# attiny85-ws2812b-v1.net
KiCad netlist of a schematic drawn in EAGLE
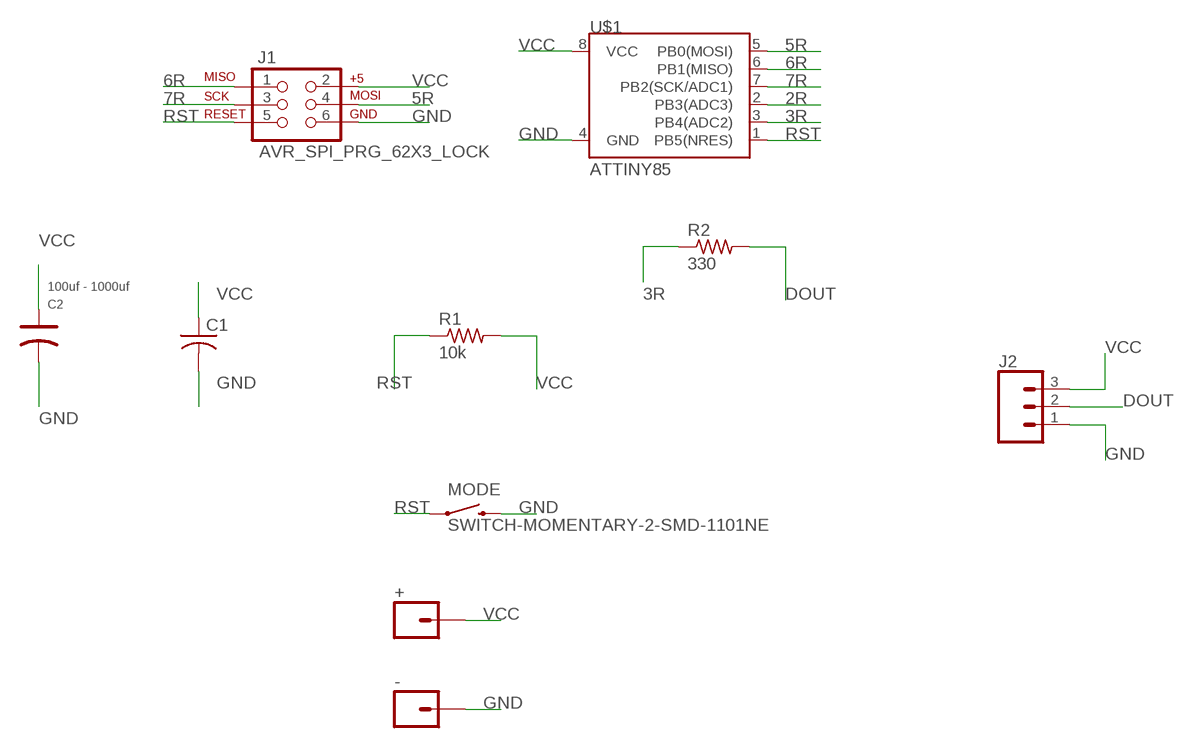
[diagram p0: schematic, sheet 1]

(export (version "E")
  (design (tool "Eeschema 10.0.6"))
  (components
    (comp (ref "+")
      (value "CONN_01PTH_LONGPAD")
      (footprint "eagle-import:1X01_LONGPAD")
      (libsource (lib "eagle-import") (part "CONN_01PTH_LONGPAD"))
    )
    (comp (ref "-")
      (value "CONN_01PTH_LONGPAD")
      (footprint "eagle-import:1X01_LONGPAD")
      (libsource (lib "eagle-import") (part "CONN_01PTH_LONGPAD"))
    )
    (comp (ref "C1")
      (value "C-USC0805K")
      (footprint "eagle-import:C0805K")
      (libsource (lib "eagle-import") (part "C-USC0805K"))
    )
    (comp (ref "C2")
      (value "100uf - 1000uf")
      (footprint "eagle-import:PC-D5.3MM")
      (fields (field (name "MPN") "KS 100uF/16V"))
      (libsource (lib "eagle-import") (part "DIP-ALUMINUM-100UF-16V(D5-H7MM)"))
    )
    (comp (ref "J1")
      (value "AVR_SPI_PRG_62X3_LOCK")
      (footprint "eagle-import:2X3_LOCK")
      (libsource (lib "eagle-import") (part "AVR_SPI_PRG_62X3_LOCK"))
    )
    (comp (ref "J2")
      (value "CONN_03LOCK_LONGPADS")
      (footprint "eagle-import:1X03_LOCK_LONGPADS")
      (libsource (lib "eagle-import") (part "CONN_03LOCK_LONGPADS"))
    )
    (comp (ref "MODE")
      (value "SWITCH-MOMENTARY-2-SMD-1101NE")
      (footprint "eagle-import:TACTILE-SWITCH-1101NE")
      (libsource (lib "eagle-import") (part "SWITCH-MOMENTARY-2-SMD-1101NE"))
    )
    (comp (ref "R1")
      (value "10k")
      (footprint "eagle-import:M0805")
      (libsource (lib "eagle-import") (part "R-US_M0805"))
    )
    (comp (ref "R2")
      (value "330")
      (footprint "eagle-import:M0805")
      (libsource (lib "eagle-import") (part "R-US_M0805"))
    )
    (comp (ref "U$1")
      (value "ATTINY85")
      (footprint "eagle-import:SO08-EIAJ")
      (libsource (lib "eagle-import") (part "ATTINY45"))
    )
  )
  (nets
    (net (code "1") (name "/2R") (class "Default")
      (node (ref "U$1") (pin "2") (pinfunction "PB3(ADC3)_2") (pintype "bidirectional"))
    )
    (net (code "2") (name "/3R") (class "Default")
      (node (ref "R2") (pin "1") (pinfunction "1_1") (pintype "passive"))
      (node (ref "U$1") (pin "3") (pinfunction "PB4(ADC2)_3") (pintype "bidirectional"))
    )
    (net (code "3") (name "/5R") (class "Default")
      (node (ref "J1") (pin "4") (pinfunction "4_4") (pintype "passive"))
      (node (ref "U$1") (pin "5") (pinfunction "PB0(MOSI)_5") (pintype "bidirectional"))
    )
    (net (code "4") (name "/6R") (class "Default")
      (node (ref "J1") (pin "1") (pinfunction "1_1") (pintype "passive"))
      (node (ref "U$1") (pin "6") (pinfunction "PB1(MISO)_6") (pintype "bidirectional"))
    )
    (net (code "5") (name "/7R") (class "Default")
      (node (ref "J1") (pin "3") (pinfunction "3_3") (pintype "passive"))
      (node (ref "U$1") (pin "7") (pinfunction "PB2(SCK/ADC1)_7") (pintype "bidirectional"))
    )
    (net (code "6") (name "/DOUT") (class "Default")
      (node (ref "J2") (pin "2") (pinfunction "2_2") (pintype "passive"))
      (node (ref "R2") (pin "2") (pinfunction "2_2") (pintype "passive"))
    )
    (net (code "7") (name "/GND") (class "Default")
      (node (ref "-") (pin "1") (pinfunction "1_1") (pintype "passive"))
      (node (ref "C1") (pin "2") (pinfunction "2_2") (pintype "passive"))
      (node (ref "C2") (pin "-") (pinfunction "-_-") (pintype "passive"))
      (node (ref "J1") (pin "6") (pinfunction "6_6") (pintype "passive"))
      (node (ref "J2") (pin "1") (pinfunction "1_1") (pintype "passive"))
      (node (ref "MODE") (pin "P$2") (pinfunction "2_P$2") (pintype "passive"))
      (node (ref "U$1") (pin "4") (pinfunction "GND_4") (pintype "bidirectional"))
    )
    (net (code "8") (name "/RST") (class "Default")
      (node (ref "J1") (pin "5") (pinfunction "5_5") (pintype "passive"))
      (node (ref "MODE") (pin "P$1") (pinfunction "1_P$1") (pintype "passive"))
      (node (ref "R1") (pin "1") (pinfunction "1_1") (pintype "passive"))
      (node (ref "U$1") (pin "1") (pinfunction "PB5(NRES)_1") (pintype "bidirectional"))
    )
    (net (code "9") (name "/VCC") (class "Default")
      (node (ref "+") (pin "1") (pinfunction "1_1") (pintype "passive"))
      (node (ref "C1") (pin "1") (pinfunction "1_1") (pintype "passive"))
      (node (ref "C2") (pin "+") (pinfunction "+_+") (pintype "passive"))
      (node (ref "J1") (pin "2") (pinfunction "2_2") (pintype "passive"))
      (node (ref "J2") (pin "3") (pinfunction "3_3") (pintype "passive"))
      (node (ref "R1") (pin "2") (pinfunction "2_2") (pintype "passive"))
      (node (ref "U$1") (pin "8") (pinfunction "VCC_8") (pintype "bidirectional"))
    )
  )
)
